# bbc.net
KiCad netlist of a schematic drawn in EAGLE
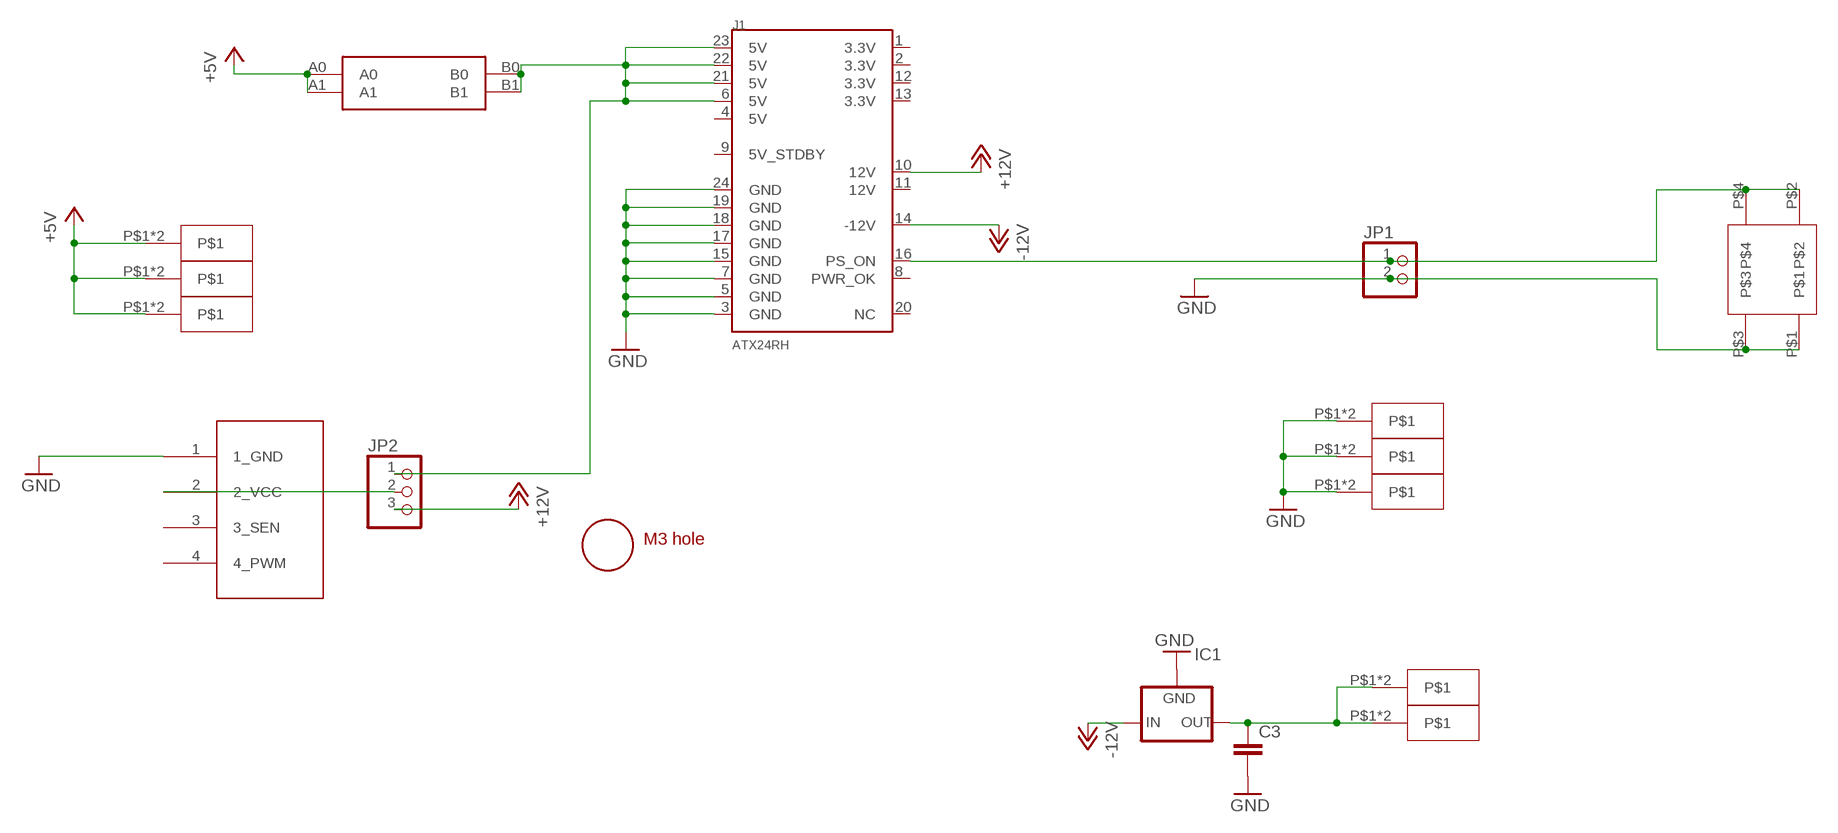
[diagram p0: schematic, sheet 1]

(export (version "E")
  (design (tool "Eeschema 10.0.6"))
  (components
    (comp (ref "C3")
      (value "C5/2.5")
      (footprint "eagle-import:C5B2.5")
      (libsource (lib "eagle-import") (part "C5/2.5"))
    )
    (comp (ref "IC1")
      (value "79XXS")
      (footprint "eagle-import:79XXS")
      (libsource (lib "eagle-import") (part "79XXS"))
    )
    (comp (ref "J1")
      (value "ATX24RH")
      (footprint "eagle-import:ATX24_RIGHT_ANGLE")
      (libsource (lib "eagle-import") (part "ATX24RH"))
    )
    (comp (ref "JP1")
      (value "PINHD-1X2")
      (footprint "eagle-import:1X02")
      (libsource (lib "eagle-import") (part "PINHD-1X2"))
    )
    (comp (ref "JP2")
      (value "PINHD-1X3")
      (footprint "eagle-import:1X03")
      (libsource (lib "eagle-import") (part "PINHD-1X3"))
    )
    (comp (ref "JP3")
      (value "4PIN_FAN")
      (footprint "eagle-import:1X04")
      (libsource (lib "eagle-import") (part "4PIN_FAN"))
    )
    (comp (ref "U$1")
      (value "CAR_FUSE_HOLDER3IN1")
      (footprint "eagle-import:FUSE_HOLDER_3IN1")
      (libsource (lib "eagle-import") (part "CAR_FUSE_HOLDER3IN1"))
    )
    (comp (ref "U$2")
      (value "BLADE28")
      (footprint "eagle-import:2.8BLADE")
      (libsource (lib "eagle-import") (part "BLADE28"))
    )
    (comp (ref "U$3")
      (value "ROCK_SW")
      (footprint "eagle-import:ROCK_SWITCH")
      (libsource (lib "eagle-import") (part "ROCK_SW"))
    )
    (comp (ref "U$4")
      (value "M3_MOUNTING_HOLE")
      (footprint "eagle-import:M3_MOUNTING_HOLE_PACK")
      (libsource (lib "eagle-import") (part "M3_MOUNTING_HOLE"))
    )
    (comp (ref "U$5")
      (value "BLADE28")
      (footprint "eagle-import:2.8BLADE")
      (libsource (lib "eagle-import") (part "BLADE28"))
    )
    (comp (ref "U$6")
      (value "BLADE28")
      (footprint "eagle-import:2.8BLADE")
      (libsource (lib "eagle-import") (part "BLADE28"))
    )
    (comp (ref "U$7")
      (value "BLADE28")
      (footprint "eagle-import:2.8BLADE")
      (libsource (lib "eagle-import") (part "BLADE28"))
    )
    (comp (ref "U$8")
      (value "BLADE28")
      (footprint "eagle-import:2.8BLADE")
      (libsource (lib "eagle-import") (part "BLADE28"))
    )
    (comp (ref "U$9")
      (value "BLADE28")
      (footprint "eagle-import:2.8BLADE")
      (libsource (lib "eagle-import") (part "BLADE28"))
    )
    (comp (ref "U$10")
      (value "BLADE28")
      (footprint "eagle-import:2.8BLADE")
      (libsource (lib "eagle-import") (part "BLADE28"))
    )
    (comp (ref "U$11")
      (value "BLADE28")
      (footprint "eagle-import:2.8BLADE")
      (libsource (lib "eagle-import") (part "BLADE28"))
    )
  )
  (nets
    (net (code "1") (name "+5V") (class "Default")
      (node (ref "U$1") (pin "A0") (pinfunction "A0_A0") (pintype "bidirectional"))
      (node (ref "U$1") (pin "A1") (pinfunction "A1_A1") (pintype "bidirectional"))
      (node (ref "U$6") (pin "P$1") (pinfunction "P$1_P$1") (pintype "bidirectional"))
      (node (ref "U$6") (pin "P$2") (pinfunction "P$1_P$2") (pintype "bidirectional"))
      (node (ref "U$7") (pin "P$1") (pinfunction "P$1_P$1") (pintype "bidirectional"))
      (node (ref "U$7") (pin "P$2") (pinfunction "P$1_P$2") (pintype "bidirectional"))
      (node (ref "U$8") (pin "P$1") (pinfunction "P$1_P$1") (pintype "bidirectional"))
      (node (ref "U$8") (pin "P$2") (pinfunction "P$1_P$2") (pintype "bidirectional"))
    )
    (net (code "2") (name "+12V") (class "Default")
      (node (ref "J1") (pin "10") (pinfunction "12V_10") (pintype "bidirectional"))
      (node (ref "JP2") (pin "3") (pinfunction "3_3") (pintype "passive"))
    )
    (net (code "3") (name "-12V") (class "Default")
      (node (ref "IC1") (pin "IN") (pinfunction "IN_IN") (pintype "input"))
      (node (ref "J1") (pin "14") (pinfunction "-12V_14") (pintype "bidirectional"))
    )
    (net (code "4") (name "GND") (class "Default")
      (node (ref "C3") (pin "2") (pinfunction "2_2") (pintype "passive"))
      (node (ref "IC1") (pin "GND") (pinfunction "GND_GND") (pintype "input"))
      (node (ref "J1") (pin "15") (pinfunction "GND_15") (pintype "bidirectional"))
      (node (ref "J1") (pin "17") (pinfunction "GND_17") (pintype "bidirectional"))
      (node (ref "J1") (pin "18") (pinfunction "GND_18") (pintype "bidirectional"))
      (node (ref "J1") (pin "19") (pinfunction "GND_19") (pintype "bidirectional"))
      (node (ref "J1") (pin "24") (pinfunction "GND_24") (pintype "bidirectional"))
      (node (ref "J1") (pin "3") (pinfunction "GND_3") (pintype "bidirectional"))
      (node (ref "J1") (pin "5") (pinfunction "GND_5") (pintype "bidirectional"))
      (node (ref "J1") (pin "7") (pinfunction "GND_7") (pintype "bidirectional"))
      (node (ref "JP1") (pin "2") (pinfunction "2_2") (pintype "passive"))
      (node (ref "JP3") (pin "1") (pinfunction "1_GND_1") (pintype "passive"))
      (node (ref "U$10") (pin "P$1") (pinfunction "P$1_P$1") (pintype "bidirectional"))
      (node (ref "U$10") (pin "P$2") (pinfunction "P$1_P$2") (pintype "bidirectional"))
      (node (ref "U$11") (pin "P$1") (pinfunction "P$1_P$1") (pintype "bidirectional"))
      (node (ref "U$11") (pin "P$2") (pinfunction "P$1_P$2") (pintype "bidirectional"))
      (node (ref "U$3") (pin "P$1") (pinfunction "P$1_P$1") (pintype "bidirectional"))
      (node (ref "U$3") (pin "P$3") (pinfunction "P$3_P$3") (pintype "bidirectional"))
      (node (ref "U$9") (pin "P$1") (pinfunction "P$1_P$1") (pintype "bidirectional"))
      (node (ref "U$9") (pin "P$2") (pinfunction "P$1_P$2") (pintype "bidirectional"))
    )
    (net (code "5") (name "Net-(C3-Pad1)") (class "Default")
      (node (ref "C3") (pin "1") (pinfunction "1_1") (pintype "passive"))
      (node (ref "IC1") (pin "OUT") (pinfunction "OUT_OUT") (pintype "passive"))
      (node (ref "U$2") (pin "P$1") (pinfunction "P$1_P$1") (pintype "bidirectional"))
      (node (ref "U$2") (pin "P$2") (pinfunction "P$1_P$2") (pintype "bidirectional"))
      (node (ref "U$5") (pin "P$1") (pinfunction "P$1_P$1") (pintype "bidirectional"))
      (node (ref "U$5") (pin "P$2") (pinfunction "P$1_P$2") (pintype "bidirectional"))
    )
    (net (code "6") (name "Net-(J1-5V-Pad21)") (class "Default")
      (node (ref "J1") (pin "21") (pinfunction "5V_21") (pintype "bidirectional"))
      (node (ref "J1") (pin "22") (pinfunction "5V_22") (pintype "bidirectional"))
      (node (ref "J1") (pin "23") (pinfunction "5V_23") (pintype "bidirectional"))
      (node (ref "J1") (pin "6") (pinfunction "5V_6") (pintype "bidirectional"))
      (node (ref "JP2") (pin "1") (pinfunction "1_1") (pintype "passive"))
      (node (ref "U$1") (pin "B0") (pinfunction "B0_B0") (pintype "bidirectional"))
      (node (ref "U$1") (pin "B1") (pinfunction "B1_B1") (pintype "bidirectional"))
    )
    (net (code "7") (name "Net-(J1-PS_ON)") (class "Default")
      (node (ref "J1") (pin "16") (pinfunction "PS_ON_16") (pintype "bidirectional"))
      (node (ref "JP1") (pin "1") (pinfunction "1_1") (pintype "passive"))
      (node (ref "U$3") (pin "P$2") (pinfunction "P$2_P$2") (pintype "bidirectional"))
      (node (ref "U$3") (pin "P$4") (pinfunction "P$4_P$4") (pintype "bidirectional"))
    )
    (net (code "8") (name "Net-(JP3-2_VCC)") (class "Default")
      (node (ref "JP2") (pin "2") (pinfunction "2_2") (pintype "passive"))
      (node (ref "JP3") (pin "2") (pinfunction "2_VCC_2") (pintype "passive"))
    )
    (net (code "9") (name "unconnected-(J1-3.3V-Pad1)") (class "Default")
      (node (ref "J1") (pin "1") (pinfunction "3.3V_1") (pintype "bidirectional"))
    )
    (net (code "10") (name "unconnected-(J1-3.3V-Pad2)") (class "Default")
      (node (ref "J1") (pin "2") (pinfunction "3.3V_2") (pintype "bidirectional"))
    )
    (net (code "11") (name "unconnected-(J1-3.3V-Pad12)") (class "Default")
      (node (ref "J1") (pin "12") (pinfunction "3.3V_12") (pintype "bidirectional"))
    )
    (net (code "12") (name "unconnected-(J1-3.3V-Pad13)") (class "Default")
      (node (ref "J1") (pin "13") (pinfunction "3.3V_13") (pintype "bidirectional"))
    )
    (net (code "13") (name "unconnected-(J1-5V-Pad4)") (class "Default")
      (node (ref "J1") (pin "4") (pinfunction "5V_4") (pintype "bidirectional"))
    )
    (net (code "14") (name "unconnected-(J1-5V_STDBY-Pad9)") (class "Default")
      (node (ref "J1") (pin "9") (pinfunction "5V_STDBY_9") (pintype "bidirectional"))
    )
    (net (code "15") (name "unconnected-(J1-12V-Pad11)") (class "Default")
      (node (ref "J1") (pin "11") (pinfunction "12V_11") (pintype "bidirectional"))
    )
    (net (code "16") (name "unconnected-(J1-NC-Pad20)") (class "Default")
      (node (ref "J1") (pin "20") (pinfunction "NC_20") (pintype "bidirectional"))
    )
    (net (code "17") (name "unconnected-(J1-PWR_OK-Pad8)") (class "Default")
      (node (ref "J1") (pin "8") (pinfunction "PWR_OK_8") (pintype "bidirectional"))
    )
    (net (code "18") (name "unconnected-(JP3-3_SEN-Pad3)") (class "Default")
      (node (ref "JP3") (pin "3") (pinfunction "3_SEN_3") (pintype "passive"))
    )
    (net (code "19") (name "unconnected-(JP3-4_PWM-Pad4)") (class "Default")
      (node (ref "JP3") (pin "4") (pinfunction "4_PWM_4") (pintype "passive"))
    )
  )
)
